# US_SB_RS485.net
KiCad netlist of a schematic drawn in Altium Designer
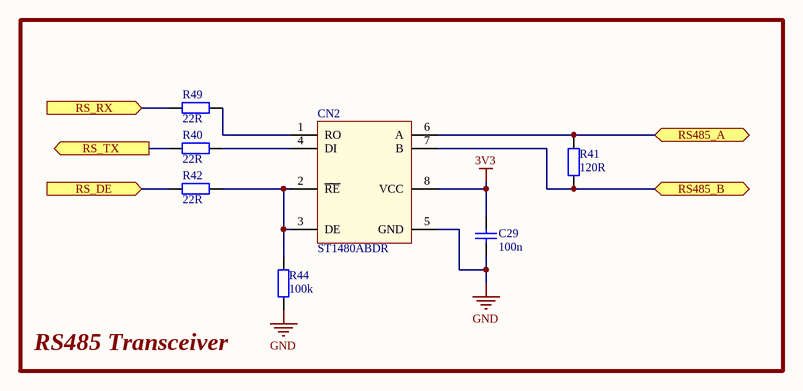
[diagram p0: US_SB_RS485.SchDoc]

(export (version "E")
  (design (tool "Eeschema 10.0.6"))
  (components
    (comp (ref "C29")
      (value "100n")
      (footprint "C0603_IPC_HD")
      (description "CAP CER 0.1UF 16V X7R 0603")
      (fields
        (field (name "MANUFACTURER") "Samsung Electro-Mechanics")
        (field (name "MANUFACTURER PART NUMBER") "CL10B104KO8NNNC")
      )
      (libsource (lib "alfasat_parts_lib") (part "CL10B104KO8NNNC"))
    )
    (comp (ref "CN2")
      (value "ST1480ABDR")
      (footprint "SOIC-8")
      (description "IC TXRX 3.3V RS485/422 8 SOIC")
      (fields (field (name "MANUFACTURER") "STMicroelectronics"))
      (libsource (lib "alfasat_parts_lib") (part "ST1480ABDR"))
    )
    (comp (ref "R40")
      (value "22R")
      (footprint "R0603_IPC_MD")
      (description "RES SMD 22 OHM 5% 1/10W 0603")
      (fields
        (field (name "MANUFACTURER") "Bourns Inc.")
        (field (name "MANUFACTURER PART NUMBER") "CR0603-JW-220ELF")
      )
      (libsource (lib "alfasat_lib") (part "CR0603-JW-220ELF"))
    )
    (comp (ref "R41")
      (value "120R")
      (footprint "R0603_IPC_MD")
      (description "RES SMD 120 OHM 5% 1/10W 0603")
      (fields
        (field (name "MANUFACTURER") "Yageo")
        (field (name "MANUFACTURER PART NUMBER") "RC0603JR-07120RL")
      )
      (libsource (lib "alfasat_lib") (part "RC0603JR-07120RL"))
    )
    (comp (ref "R42")
      (value "22R")
      (footprint "R0603_IPC_MD")
      (description "RES SMD 22 OHM 5% 1/10W 0603")
      (fields
        (field (name "MANUFACTURER") "Bourns Inc.")
        (field (name "MANUFACTURER PART NUMBER") "CR0603-JW-220ELF")
      )
      (libsource (lib "alfasat_lib") (part "CR0603-JW-220ELF"))
    )
    (comp (ref "R44")
      (value "100k")
      (footprint "R0603_IPC_MD")
      (description "RES 100K OHM 1% 1/10W 0603")
      (fields
        (field (name "MANUFACTURER") "Stackpole Electronics Inc")
        (field (name "MANUFACTURER PART NUMBER") "RMCF0603FT100K")
      )
      (libsource (lib "alfasat_lib_eps") (part "CR0603-JW-104ELF"))
    )
    (comp (ref "R49")
      (value "22R")
      (footprint "R0603_IPC_MD")
      (description "RES SMD 22 OHM 5% 1/10W 0603")
      (fields
        (field (name "MANUFACTURER") "Bourns Inc.")
        (field (name "MANUFACTURER PART NUMBER") "CR0603-JW-220ELF")
      )
      (libsource (lib "alfasat_lib") (part "CR0603-JW-220ELF"))
    )
  )
  (nets
    (net (code "1") (name "/RS485_A") (class "Default")
      (node (ref "CN2") (pin "6") (pinfunction "A_6") (pintype "passive"))
      (node (ref "R41") (pin "2") (pinfunction "2_2") (pintype "passive"))
    )
    (net (code "2") (name "/RS485_B") (class "Default")
      (node (ref "CN2") (pin "7") (pinfunction "B_7") (pintype "passive"))
      (node (ref "R41") (pin "1") (pinfunction "1_1") (pintype "passive"))
    )
    (net (code "3") (name "/RS_DE") (class "Default")
      (node (ref "R42") (pin "1") (pinfunction "1_1") (pintype "passive"))
    )
    (net (code "4") (name "/RS_RX") (class "Default")
      (node (ref "R49") (pin "1") (pinfunction "1_1") (pintype "passive"))
    )
    (net (code "5") (name "/RS_TX") (class "Default")
      (node (ref "R40") (pin "1") (pinfunction "1_1") (pintype "passive"))
    )
    (net (code "6") (name "3V3") (class "Default")
      (node (ref "C29") (pin "2") (pinfunction "2_2") (pintype "passive"))
      (node (ref "CN2") (pin "8") (pinfunction "VCC_8") (pintype "passive"))
    )
    (net (code "7") (name "GND") (class "Default")
      (node (ref "C29") (pin "1") (pinfunction "1_1") (pintype "passive"))
      (node (ref "CN2") (pin "5") (pinfunction "GND_5") (pintype "passive"))
      (node (ref "R44") (pin "1") (pinfunction "1_1") (pintype "passive"))
    )
    (net (code "8") (name "Net-(CN2-DE)") (class "Default")
      (node (ref "CN2") (pin "2") (pinfunction "~{RE}_2") (pintype "passive"))
      (node (ref "CN2") (pin "3") (pinfunction "DE_3") (pintype "passive"))
      (node (ref "R42") (pin "2") (pinfunction "2_2") (pintype "passive"))
      (node (ref "R44") (pin "2") (pinfunction "2_2") (pintype "passive"))
    )
    (net (code "9") (name "Net-(CN2-DI)") (class "Default")
      (node (ref "CN2") (pin "4") (pinfunction "DI_4") (pintype "passive"))
      (node (ref "R40") (pin "2") (pinfunction "2_2") (pintype "passive"))
    )
    (net (code "10") (name "Net-(CN2-RO)") (class "Default")
      (node (ref "CN2") (pin "1") (pinfunction "RO_1") (pintype "passive"))
      (node (ref "R49") (pin "2") (pinfunction "2_2") (pintype "passive"))
    )
  )
)
